# Terminators.net
KiCad netlist of a schematic drawn in Altium Designer
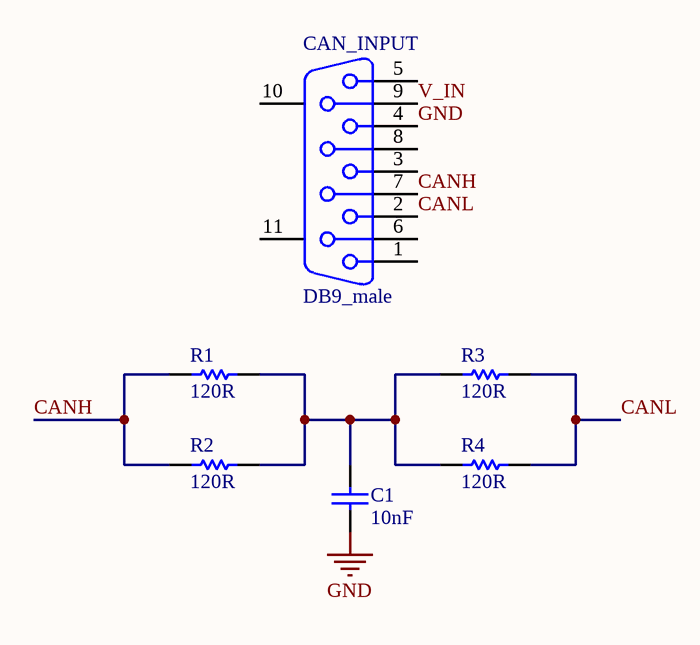
[diagram p0: Terminators.SchDoc]

(export (version "E")
  (design (tool "Eeschema 10.0.6"))
  (components
    (comp (ref "C1")
      (value "10nF")
      (footprint "CC0603")
      (description "0603 Capacitor")
      (fields (field (name "PART NUMBER") "10nF_CC0603"))
      (libsource (lib "ECE_Component_Library_2") (part "10nF_CC0603"))
    )
    (comp (ref "CAN_INPUT")
      (value "DB9_male")
      (footprint "db9_male")
      (description "DB9 Male Connecter")
      (fields (field (name "PART NUMBER") "db9_male"))
      (libsource (lib "ECE_Component_Library_2") (part "db9_male"))
    )
    (comp (ref "R1")
      (value "120R")
      (footprint "R0603")
      (description "0603 Resistor")
      (fields (field (name "PART NUMBER") "120R_R0603"))
      (libsource (lib "ECE_Component_Library_2") (part "120R_R0603"))
    )
    (comp (ref "R2")
      (value "120R")
      (footprint "R0603")
      (description "0603 Resistor")
      (fields (field (name "PART NUMBER") "120R_R0603"))
      (libsource (lib "ECE_Component_Library_2") (part "120R_R0603"))
    )
    (comp (ref "R3")
      (value "120R")
      (footprint "R0603")
      (description "0603 Resistor")
      (fields (field (name "PART NUMBER") "120R_R0603"))
      (libsource (lib "ECE_Component_Library_2") (part "120R_R0603"))
    )
    (comp (ref "R4")
      (value "120R")
      (footprint "R0603")
      (description "0603 Resistor")
      (fields (field (name "PART NUMBER") "120R_R0603"))
      (libsource (lib "ECE_Component_Library_2") (part "120R_R0603"))
    )
  )
  (nets
    (net (code "1") (name "/CANH") (class "Default")
      (node (ref "CAN_INPUT") (pin "7") (pinfunction "7_7") (pintype "passive"))
      (node (ref "R1") (pin "1") (pinfunction "1_1") (pintype "passive"))
      (node (ref "R2") (pin "1") (pinfunction "1_1") (pintype "passive"))
    )
    (net (code "2") (name "/CANL") (class "Default")
      (node (ref "CAN_INPUT") (pin "2") (pinfunction "2_2") (pintype "passive"))
      (node (ref "R3") (pin "2") (pinfunction "2_2") (pintype "passive"))
      (node (ref "R4") (pin "2") (pinfunction "2_2") (pintype "passive"))
    )
    (net (code "3") (name "/V_IN") (class "Default")
      (node (ref "CAN_INPUT") (pin "9") (pinfunction "9_9") (pintype "passive"))
    )
    (net (code "4") (name "GND") (class "Default")
      (node (ref "C1") (pin "1") (pinfunction "1_1") (pintype "passive"))
      (node (ref "CAN_INPUT") (pin "4") (pinfunction "4_4") (pintype "passive"))
    )
    (net (code "5") (name "Net-(C1-Pad2)") (class "Default")
      (node (ref "C1") (pin "2") (pinfunction "2_2") (pintype "passive"))
      (node (ref "R1") (pin "2") (pinfunction "2_2") (pintype "passive"))
      (node (ref "R2") (pin "2") (pinfunction "2_2") (pintype "passive"))
      (node (ref "R3") (pin "1") (pinfunction "1_1") (pintype "passive"))
      (node (ref "R4") (pin "1") (pinfunction "1_1") (pintype "passive"))
    )
    (net (code "6") (name "unconnected-(CAN_INPUT-MH1-Pad10)") (class "Default")
      (node (ref "CAN_INPUT") (pin "10") (pinfunction "MH1_10") (pintype "passive"))
    )
    (net (code "7") (name "unconnected-(CAN_INPUT-MH2-Pad11)") (class "Default")
      (node (ref "CAN_INPUT") (pin "11") (pinfunction "MH2_11") (pintype "passive"))
    )
    (net (code "8") (name "unconnected-(CAN_INPUT-Pad1)") (class "Default")
      (node (ref "CAN_INPUT") (pin "1") (pinfunction "1_1") (pintype "passive"))
    )
    (net (code "9") (name "unconnected-(CAN_INPUT-Pad3)") (class "Default")
      (node (ref "CAN_INPUT") (pin "3") (pinfunction "3_3") (pintype "passive"))
    )
    (net (code "10") (name "unconnected-(CAN_INPUT-Pad5)") (class "Default")
      (node (ref "CAN_INPUT") (pin "5") (pinfunction "5_5") (pintype "passive"))
    )
    (net (code "11") (name "unconnected-(CAN_INPUT-Pad6)") (class "Default")
      (node (ref "CAN_INPUT") (pin "6") (pinfunction "6_6") (pintype "passive"))
    )
    (net (code "12") (name "unconnected-(CAN_INPUT-Pad8)") (class "Default")
      (node (ref "CAN_INPUT") (pin "8") (pinfunction "8_8") (pintype "passive"))
    )
  )
)
